# Magnetic-Charger.net
KiCad netlist of a schematic drawn in Altium Designer
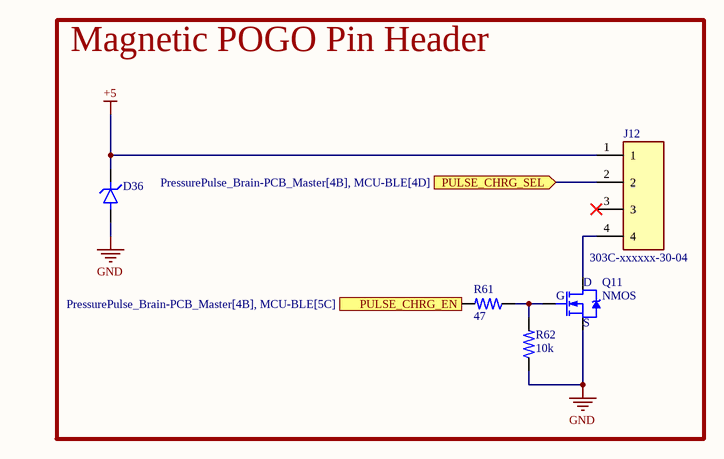
[diagram p0: Magnetic-Charger.SchDoc]

(export (version "E")
  (design (tool "Eeschema 10.0.6"))
  (components
    (comp (ref "D36")
      (value "RCLAMP0521P.TCT")
      (footprint "PressurePulse:BDFN2C051V40")
      (description "25V Clamp 4A (8/20µs) Ipp Tvs Diode Surface Mount SLP1006P2")
      (fields (field (name "MFR") "BORN"))
      (libsource (lib "PressurePulse") (part "TVS DIODE"))
    )
    (comp (ref "J12")
      (value "303C-xxxxxx-30-04")
      (footprint "PressurePulse:MAG POGO - 4 POS MALE")
      (description "MAGNETIC POGO 4POS")
      (fields (field (name "MFR") "ATTEND Technology"))
      (libsource (lib "PressurePulse") (part "303C-xxxxxx-30-04"))
    )
    (comp (ref "Q11")
      (value "NMOS")
      (footprint "PressurePulse:SOT-23")
      (description "100V 1.6A 1.3W 220mΩ@10V,1.6A N Channel SOT-23  MOSFETs ROHS")
      (fields (field (name "MFR") "Infineon"))
      (libsource (lib "PressurePulse") (part "NMOS"))
    )
    (comp (ref "R61")
      (value "47")
      (footprint "PressurePulse:0402R")
      (description "Resistor")
      (fields (field (name "Comment") "RES"))
      (libsource (lib "PressurePulse") (part "RES"))
    )
    (comp (ref "R62")
      (value "10k")
      (footprint "PressurePulse:0402R")
      (description "Resistor")
      (fields (field (name "Comment") "RES"))
      (libsource (lib "PressurePulse") (part "RES"))
    )
  )
  (nets
    (net (code "1") (name "+5") (class "Default")
      (node (ref "D36") (pin "K") (pinfunction "K_K") (pintype "passive"))
      (node (ref "J12") (pin "1") (pinfunction "1_1") (pintype "passive"))
    )
    (net (code "2") (name "/PULSE_CHRG_EN") (class "Default")
      (node (ref "R61") (pin "2") (pinfunction "2_2") (pintype "passive"))
    )
    (net (code "3") (name "/PULSE_CHRG_SEL") (class "Default")
      (node (ref "J12") (pin "2") (pinfunction "2_2") (pintype "passive"))
    )
    (net (code "4") (name "GND") (class "Default")
      (node (ref "D36") (pin "A") (pinfunction "A_A") (pintype "passive"))
      (node (ref "Q11") (pin "S") (pinfunction "S_S") (pintype "passive"))
      (node (ref "R62") (pin "1") (pinfunction "1_1") (pintype "passive"))
    )
    (net (code "5") (name "Net-(J12-Pad4)") (class "Default")
      (node (ref "J12") (pin "4") (pinfunction "4_4") (pintype "passive"))
      (node (ref "Q11") (pin "D") (pinfunction "D_D") (pintype "passive"))
    )
    (net (code "6") (name "Net-(Q11-PadG)") (class "Default")
      (node (ref "Q11") (pin "G") (pinfunction "G_G") (pintype "passive"))
      (node (ref "R61") (pin "1") (pinfunction "1_1") (pintype "passive"))
      (node (ref "R62") (pin "2") (pinfunction "2_2") (pintype "passive"))
    )
    (net (code "7") (name "unconnected-(J12-Pad3)") (class "Default")
      (node (ref "J12") (pin "3") (pinfunction "3_3") (pintype "passive+no_connect"))
    )
  )
)
